# Digital_Port_K_Button.net
KiCad netlist of a schematic drawn in Altium Designer
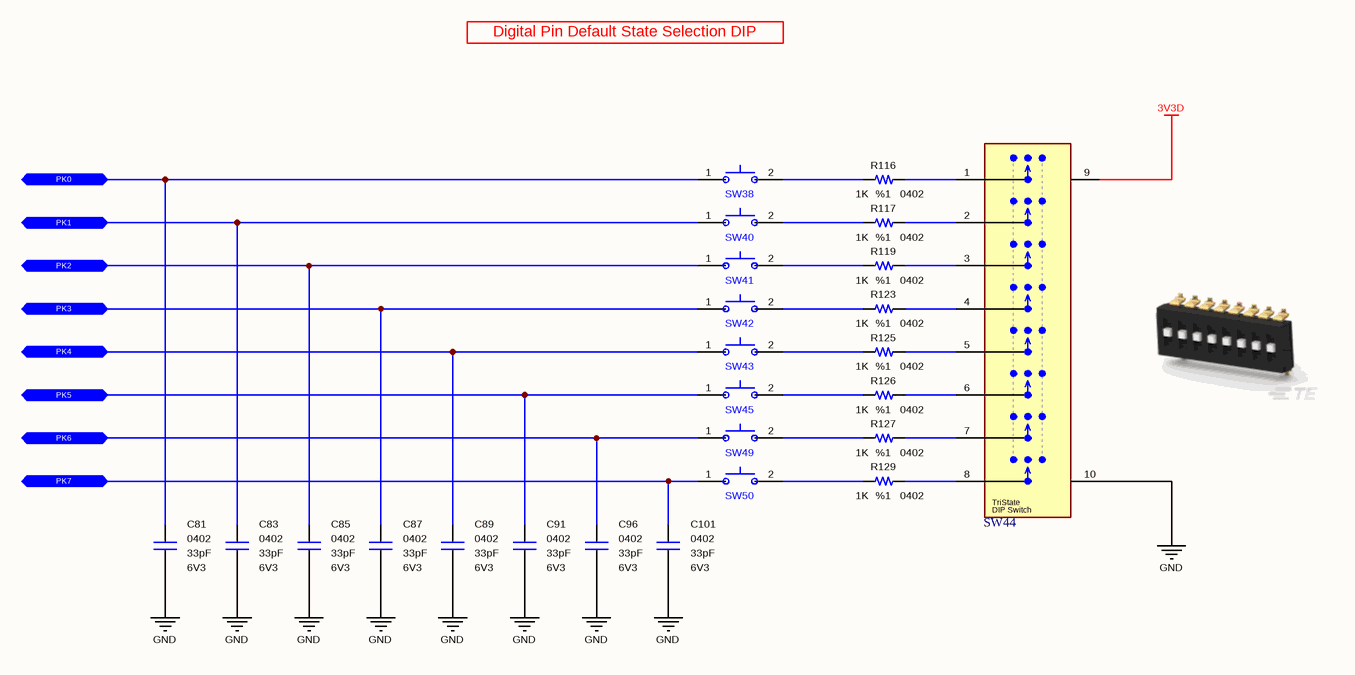
[diagram p0: Digital Port K Button.SchDoc]

(export (version "E")
  (design (tool "Eeschema 10.0.6"))
  (components
    (comp (ref "C81")
      (value "33pF")
      (footprint "CAPACITOR_0402")
      (description "Capacitor - 33pF [0402] (Ceramic)")
      (fields
        (field (name "MANUFACTURER PART NUMBER") "C0402C330J9RACAUTO")
        (field (name "MOUSER PART NUMBER") "80-C0402C330J9RAUTO")
        (field (name "CASE") "0402")
        (field (name "VOLTAGE") "6V3")
      )
      (libsource (lib "Ovoo_Library") (part "Capacitor - 33pF [0402-6V3]"))
    )
    (comp (ref "C83")
      (value "33pF")
      (footprint "CAPACITOR_0402")
      (description "Capacitor - 33pF [0402] (Ceramic)")
      (fields
        (field (name "MANUFACTURER PART NUMBER") "C0402C330J9RACAUTO")
        (field (name "MOUSER PART NUMBER") "80-C0402C330J9RAUTO")
        (field (name "CASE") "0402")
        (field (name "VOLTAGE") "6V3")
      )
      (libsource (lib "Ovoo_Library") (part "Capacitor - 33pF [0402-6V3]"))
    )
    (comp (ref "C85")
      (value "33pF")
      (footprint "CAPACITOR_0402")
      (description "Capacitor - 33pF [0402] (Ceramic)")
      (fields
        (field (name "MANUFACTURER PART NUMBER") "C0402C330J9RACAUTO")
        (field (name "MOUSER PART NUMBER") "80-C0402C330J9RAUTO")
        (field (name "CASE") "0402")
        (field (name "VOLTAGE") "6V3")
      )
      (libsource (lib "Ovoo_Library") (part "Capacitor - 33pF [0402-6V3]"))
    )
    (comp (ref "C87")
      (value "33pF")
      (footprint "CAPACITOR_0402")
      (description "Capacitor - 33pF [0402] (Ceramic)")
      (fields
        (field (name "MANUFACTURER PART NUMBER") "C0402C330J9RACAUTO")
        (field (name "MOUSER PART NUMBER") "80-C0402C330J9RAUTO")
        (field (name "CASE") "0402")
        (field (name "VOLTAGE") "6V3")
      )
      (libsource (lib "Ovoo_Library") (part "Capacitor - 33pF [0402-6V3]"))
    )
    (comp (ref "C89")
      (value "33pF")
      (footprint "CAPACITOR_0402")
      (description "Capacitor - 33pF [0402] (Ceramic)")
      (fields
        (field (name "MANUFACTURER PART NUMBER") "C0402C330J9RACAUTO")
        (field (name "MOUSER PART NUMBER") "80-C0402C330J9RAUTO")
        (field (name "CASE") "0402")
        (field (name "VOLTAGE") "6V3")
      )
      (libsource (lib "Ovoo_Library") (part "Capacitor - 33pF [0402-6V3]"))
    )
    (comp (ref "C91")
      (value "33pF")
      (footprint "CAPACITOR_0402")
      (description "Capacitor - 33pF [0402] (Ceramic)")
      (fields
        (field (name "MANUFACTURER PART NUMBER") "C0402C330J9RACAUTO")
        (field (name "MOUSER PART NUMBER") "80-C0402C330J9RAUTO")
        (field (name "CASE") "0402")
        (field (name "VOLTAGE") "6V3")
      )
      (libsource (lib "Ovoo_Library") (part "Capacitor - 33pF [0402-6V3]"))
    )
    (comp (ref "C96")
      (value "33pF")
      (footprint "CAPACITOR_0402")
      (description "Capacitor - 33pF [0402] (Ceramic)")
      (fields
        (field (name "MANUFACTURER PART NUMBER") "C0402C330J9RACAUTO")
        (field (name "MOUSER PART NUMBER") "80-C0402C330J9RAUTO")
        (field (name "CASE") "0402")
        (field (name "VOLTAGE") "6V3")
      )
      (libsource (lib "Ovoo_Library") (part "Capacitor - 33pF [0402-6V3]"))
    )
    (comp (ref "C101")
      (value "33pF")
      (footprint "CAPACITOR_0402")
      (description "Capacitor - 33pF [0402] (Ceramic)")
      (fields
        (field (name "MANUFACTURER PART NUMBER") "C0402C330J9RACAUTO")
        (field (name "MOUSER PART NUMBER") "80-C0402C330J9RAUTO")
        (field (name "CASE") "0402")
        (field (name "VOLTAGE") "6V3")
      )
      (libsource (lib "Ovoo_Library") (part "Capacitor - 33pF [0402-6V3]"))
    )
    (comp (ref "R116")
      (value "1K")
      (footprint "RESISTOR_0402")
      (description "Thick Film Resistors - SMD 1/16 W 1.0 Kohms 1%")
      (fields
        (field (name "MANUFACTURER PART NUMBER") "CRCW04021K00FKED")
        (field (name "MOUSER PART NUMBER") "71-CRCW0402-1.0K-E3")
        (field (name "TOLERANCE") "%1")
        (field (name "CASE") "0402")
      )
      (libsource (lib "Ovoo_Library") (part "Resistor - 1K"))
    )
    (comp (ref "R117")
      (value "1K")
      (footprint "RESISTOR_0402")
      (description "Thick Film Resistors - SMD 1/16 W 1.0 Kohms 1%")
      (fields
        (field (name "MANUFACTURER PART NUMBER") "CRCW04021K00FKED")
        (field (name "MOUSER PART NUMBER") "71-CRCW0402-1.0K-E3")
        (field (name "TOLERANCE") "%1")
        (field (name "CASE") "0402")
      )
      (libsource (lib "Ovoo_Library") (part "Resistor - 1K"))
    )
    (comp (ref "R119")
      (value "1K")
      (footprint "RESISTOR_0402")
      (description "Thick Film Resistors - SMD 1/16 W 1.0 Kohms 1%")
      (fields
        (field (name "MANUFACTURER PART NUMBER") "CRCW04021K00FKED")
        (field (name "MOUSER PART NUMBER") "71-CRCW0402-1.0K-E3")
        (field (name "TOLERANCE") "%1")
        (field (name "CASE") "0402")
      )
      (libsource (lib "Ovoo_Library") (part "Resistor - 1K"))
    )
    (comp (ref "R123")
      (value "1K")
      (footprint "RESISTOR_0402")
      (description "Thick Film Resistors - SMD 1/16 W 1.0 Kohms 1%")
      (fields
        (field (name "MANUFACTURER PART NUMBER") "CRCW04021K00FKED")
        (field (name "MOUSER PART NUMBER") "71-CRCW0402-1.0K-E3")
        (field (name "TOLERANCE") "%1")
        (field (name "CASE") "0402")
      )
      (libsource (lib "Ovoo_Library") (part "Resistor - 1K"))
    )
    (comp (ref "R125")
      (value "1K")
      (footprint "RESISTOR_0402")
      (description "Thick Film Resistors - SMD 1/16 W 1.0 Kohms 1%")
      (fields
        (field (name "MANUFACTURER PART NUMBER") "CRCW04021K00FKED")
        (field (name "MOUSER PART NUMBER") "71-CRCW0402-1.0K-E3")
        (field (name "TOLERANCE") "%1")
        (field (name "CASE") "0402")
      )
      (libsource (lib "Ovoo_Library") (part "Resistor - 1K"))
    )
    (comp (ref "R126")
      (value "1K")
      (footprint "RESISTOR_0402")
      (description "Thick Film Resistors - SMD 1/16 W 1.0 Kohms 1%")
      (fields
        (field (name "MANUFACTURER PART NUMBER") "CRCW04021K00FKED")
        (field (name "MOUSER PART NUMBER") "71-CRCW0402-1.0K-E3")
        (field (name "TOLERANCE") "%1")
        (field (name "CASE") "0402")
      )
      (libsource (lib "Ovoo_Library") (part "Resistor - 1K"))
    )
    (comp (ref "R127")
      (value "1K")
      (footprint "RESISTOR_0402")
      (description "Thick Film Resistors - SMD 1/16 W 1.0 Kohms 1%")
      (fields
        (field (name "MANUFACTURER PART NUMBER") "CRCW04021K00FKED")
        (field (name "MOUSER PART NUMBER") "71-CRCW0402-1.0K-E3")
        (field (name "TOLERANCE") "%1")
        (field (name "CASE") "0402")
      )
      (libsource (lib "Ovoo_Library") (part "Resistor - 1K"))
    )
    (comp (ref "R129")
      (value "1K")
      (footprint "RESISTOR_0402")
      (description "Thick Film Resistors - SMD 1/16 W 1.0 Kohms 1%")
      (fields
        (field (name "MANUFACTURER PART NUMBER") "CRCW04021K00FKED")
        (field (name "MOUSER PART NUMBER") "71-CRCW0402-1.0K-E3")
        (field (name "TOLERANCE") "%1")
        (field (name "CASE") "0402")
      )
      (libsource (lib "Ovoo_Library") (part "Resistor - 1K"))
    )
    (comp (ref "SW38")
      (value "Tactile Switches")
      (footprint "PTS526_Switch")
      (description "Tactile Switches 50mA 12VDC, 5.2x5.2mm, 0.8mm H, 260gf, G leads.")
      (fields
        (field (name "MANUFACTURER PART NUMBER") "PTS526 SK08 SMTR2 LFS")
        (field (name "MOUSER PART NUMBER") "611-PTS526SK08SMTR2L")
      )
      (libsource (lib "Ovoo_Library") (part "Switch - Tactile"))
    )
    (comp (ref "SW40")
      (value "Tactile Switches")
      (footprint "PTS526_Switch")
      (description "Tactile Switches 50mA 12VDC, 5.2x5.2mm, 0.8mm H, 260gf, G leads.")
      (fields
        (field (name "MANUFACTURER PART NUMBER") "PTS526 SK08 SMTR2 LFS")
        (field (name "MOUSER PART NUMBER") "611-PTS526SK08SMTR2L")
      )
      (libsource (lib "Ovoo_Library") (part "Switch - Tactile"))
    )
    (comp (ref "SW41")
      (value "Tactile Switches")
      (footprint "PTS526_Switch")
      (description "Tactile Switches 50mA 12VDC, 5.2x5.2mm, 0.8mm H, 260gf, G leads.")
      (fields
        (field (name "MANUFACTURER PART NUMBER") "PTS526 SK08 SMTR2 LFS")
        (field (name "MOUSER PART NUMBER") "611-PTS526SK08SMTR2L")
      )
      (libsource (lib "Ovoo_Library") (part "Switch - Tactile"))
    )
    (comp (ref "SW42")
      (value "Tactile Switches")
      (footprint "PTS526_Switch")
      (description "Tactile Switches 50mA 12VDC, 5.2x5.2mm, 0.8mm H, 260gf, G leads.")
      (fields
        (field (name "MANUFACTURER PART NUMBER") "PTS526 SK08 SMTR2 LFS")
        (field (name "MOUSER PART NUMBER") "611-PTS526SK08SMTR2L")
      )
      (libsource (lib "Ovoo_Library") (part "Switch - Tactile"))
    )
    (comp (ref "SW43")
      (value "Tactile Switches")
      (footprint "PTS526_Switch")
      (description "Tactile Switches 50mA 12VDC, 5.2x5.2mm, 0.8mm H, 260gf, G leads.")
      (fields
        (field (name "MANUFACTURER PART NUMBER") "PTS526 SK08 SMTR2 LFS")
        (field (name "MOUSER PART NUMBER") "611-PTS526SK08SMTR2L")
      )
      (libsource (lib "Ovoo_Library") (part "Switch - Tactile"))
    )
    (comp (ref "SW44")
      (value "DIP Switches/SIP Switches")
      (footprint "TDS08SGNNTR04")
      (description "DIP Switches/SIP Switches TRI-STATE DIP 8P G RAISED T&R")
      (fields
        (field (name "MANUFACTURER PART NUMBER") "TDS08SGNNTR04")
        (field (name "MOUSER PART NUMBER") "506-TDS08SGNNTR04")
      )
      (libsource (lib "Ovoo_Library") (part "Switch - DIP Switch (8 Pole TriState)"))
    )
    (comp (ref "SW45")
      (value "Tactile Switches")
      (footprint "PTS526_Switch")
      (description "Tactile Switches 50mA 12VDC, 5.2x5.2mm, 0.8mm H, 260gf, G leads.")
      (fields
        (field (name "MANUFACTURER PART NUMBER") "PTS526 SK08 SMTR2 LFS")
        (field (name "MOUSER PART NUMBER") "611-PTS526SK08SMTR2L")
      )
      (libsource (lib "Ovoo_Library") (part "Switch - Tactile"))
    )
    (comp (ref "SW49")
      (value "Tactile Switches")
      (footprint "PTS526_Switch")
      (description "Tactile Switches 50mA 12VDC, 5.2x5.2mm, 0.8mm H, 260gf, G leads.")
      (fields
        (field (name "MANUFACTURER PART NUMBER") "PTS526 SK08 SMTR2 LFS")
        (field (name "MOUSER PART NUMBER") "611-PTS526SK08SMTR2L")
      )
      (libsource (lib "Ovoo_Library") (part "Switch - Tactile"))
    )
    (comp (ref "SW50")
      (value "Tactile Switches")
      (footprint "PTS526_Switch")
      (description "Tactile Switches 50mA 12VDC, 5.2x5.2mm, 0.8mm H, 260gf, G leads.")
      (fields
        (field (name "MANUFACTURER PART NUMBER") "PTS526 SK08 SMTR2 LFS")
        (field (name "MOUSER PART NUMBER") "611-PTS526SK08SMTR2L")
      )
      (libsource (lib "Ovoo_Library") (part "Switch - Tactile"))
    )
  )
  (nets
    (net (code "1") (name "/PK0") (class "Default")
      (node (ref "C81") (pin "2") (pinfunction "2_2") (pintype "passive"))
      (node (ref "SW38") (pin "1") (pinfunction "NC_1") (pintype "passive"))
    )
    (net (code "2") (name "/PK1") (class "Default")
      (node (ref "C83") (pin "2") (pinfunction "2_2") (pintype "passive"))
      (node (ref "SW40") (pin "1") (pinfunction "NC_1") (pintype "passive"))
    )
    (net (code "3") (name "/PK2") (class "Default")
      (node (ref "C85") (pin "2") (pinfunction "2_2") (pintype "passive"))
      (node (ref "SW41") (pin "1") (pinfunction "NC_1") (pintype "passive"))
    )
    (net (code "4") (name "/PK3") (class "Default")
      (node (ref "C87") (pin "2") (pinfunction "2_2") (pintype "passive"))
      (node (ref "SW42") (pin "1") (pinfunction "NC_1") (pintype "passive"))
    )
    (net (code "5") (name "/PK4") (class "Default")
      (node (ref "C89") (pin "2") (pinfunction "2_2") (pintype "passive"))
      (node (ref "SW43") (pin "1") (pinfunction "NC_1") (pintype "passive"))
    )
    (net (code "6") (name "/PK5") (class "Default")
      (node (ref "C91") (pin "2") (pinfunction "2_2") (pintype "passive"))
      (node (ref "SW45") (pin "1") (pinfunction "NC_1") (pintype "passive"))
    )
    (net (code "7") (name "/PK6") (class "Default")
      (node (ref "C96") (pin "2") (pinfunction "2_2") (pintype "passive"))
      (node (ref "SW49") (pin "1") (pinfunction "NC_1") (pintype "passive"))
    )
    (net (code "8") (name "/PK7") (class "Default")
      (node (ref "C101") (pin "2") (pinfunction "2_2") (pintype "passive"))
      (node (ref "SW50") (pin "1") (pinfunction "NC_1") (pintype "passive"))
    )
    (net (code "9") (name "3V3D") (class "Default")
      (node (ref "SW44") (pin "9") (pinfunction "VCC_9") (pintype "passive"))
    )
    (net (code "10") (name "GND") (class "Default")
      (node (ref "C101") (pin "1") (pinfunction "1_1") (pintype "passive"))
      (node (ref "C81") (pin "1") (pinfunction "1_1") (pintype "passive"))
      (node (ref "C83") (pin "1") (pinfunction "1_1") (pintype "passive"))
      (node (ref "C85") (pin "1") (pinfunction "1_1") (pintype "passive"))
      (node (ref "C87") (pin "1") (pinfunction "1_1") (pintype "passive"))
      (node (ref "C89") (pin "1") (pinfunction "1_1") (pintype "passive"))
      (node (ref "C91") (pin "1") (pinfunction "1_1") (pintype "passive"))
      (node (ref "C96") (pin "1") (pinfunction "1_1") (pintype "passive"))
      (node (ref "SW44") (pin "10") (pinfunction "GND_10") (pintype "passive"))
    )
    (net (code "11") (name "Net-(R116-Pad1)") (class "Default")
      (node (ref "R116") (pin "1") (pinfunction "1_1") (pintype "passive"))
      (node (ref "SW44") (pin "1") (pinfunction "1_1") (pintype "passive"))
    )
    (net (code "12") (name "Net-(R117-Pad1)") (class "Default")
      (node (ref "R117") (pin "1") (pinfunction "1_1") (pintype "passive"))
      (node (ref "SW44") (pin "2") (pinfunction "2_2") (pintype "passive"))
    )
    (net (code "13") (name "Net-(R119-Pad1)") (class "Default")
      (node (ref "R119") (pin "1") (pinfunction "1_1") (pintype "passive"))
      (node (ref "SW44") (pin "3") (pinfunction "3_3") (pintype "passive"))
    )
    (net (code "14") (name "Net-(R123-Pad1)") (class "Default")
      (node (ref "R123") (pin "1") (pinfunction "1_1") (pintype "passive"))
      (node (ref "SW44") (pin "4") (pinfunction "4_4") (pintype "passive"))
    )
    (net (code "15") (name "Net-(R125-Pad1)") (class "Default")
      (node (ref "R125") (pin "1") (pinfunction "1_1") (pintype "passive"))
      (node (ref "SW44") (pin "5") (pinfunction "5_5") (pintype "passive"))
    )
    (net (code "16") (name "Net-(R126-Pad1)") (class "Default")
      (node (ref "R126") (pin "1") (pinfunction "1_1") (pintype "passive"))
      (node (ref "SW44") (pin "6") (pinfunction "6_6") (pintype "passive"))
    )
    (net (code "17") (name "Net-(R127-Pad1)") (class "Default")
      (node (ref "R127") (pin "1") (pinfunction "1_1") (pintype "passive"))
      (node (ref "SW44") (pin "7") (pinfunction "7_7") (pintype "passive"))
    )
    (net (code "18") (name "Net-(R129-Pad1)") (class "Default")
      (node (ref "R129") (pin "1") (pinfunction "1_1") (pintype "passive"))
      (node (ref "SW44") (pin "8") (pinfunction "8_8") (pintype "passive"))
    )
    (net (code "19") (name "Net-(SW38-COM)") (class "Default")
      (node (ref "R116") (pin "2") (pinfunction "2_2") (pintype "passive"))
      (node (ref "SW38") (pin "2") (pinfunction "COM_2") (pintype "passive"))
    )
    (net (code "20") (name "Net-(SW40-COM)") (class "Default")
      (node (ref "R117") (pin "2") (pinfunction "2_2") (pintype "passive"))
      (node (ref "SW40") (pin "2") (pinfunction "COM_2") (pintype "passive"))
    )
    (net (code "21") (name "Net-(SW41-COM)") (class "Default")
      (node (ref "R119") (pin "2") (pinfunction "2_2") (pintype "passive"))
      (node (ref "SW41") (pin "2") (pinfunction "COM_2") (pintype "passive"))
    )
    (net (code "22") (name "Net-(SW42-COM)") (class "Default")
      (node (ref "R123") (pin "2") (pinfunction "2_2") (pintype "passive"))
      (node (ref "SW42") (pin "2") (pinfunction "COM_2") (pintype "passive"))
    )
    (net (code "23") (name "Net-(SW43-COM)") (class "Default")
      (node (ref "R125") (pin "2") (pinfunction "2_2") (pintype "passive"))
      (node (ref "SW43") (pin "2") (pinfunction "COM_2") (pintype "passive"))
    )
    (net (code "24") (name "Net-(SW45-COM)") (class "Default")
      (node (ref "R126") (pin "2") (pinfunction "2_2") (pintype "passive"))
      (node (ref "SW45") (pin "2") (pinfunction "COM_2") (pintype "passive"))
    )
    (net (code "25") (name "Net-(SW49-COM)") (class "Default")
      (node (ref "R127") (pin "2") (pinfunction "2_2") (pintype "passive"))
      (node (ref "SW49") (pin "2") (pinfunction "COM_2") (pintype "passive"))
    )
    (net (code "26") (name "Net-(SW50-COM)") (class "Default")
      (node (ref "R129") (pin "2") (pinfunction "2_2") (pintype "passive"))
      (node (ref "SW50") (pin "2") (pinfunction "COM_2") (pintype "passive"))
    )
  )
)
